# Jebao.net
KiCad netlist of a schematic drawn in EAGLE
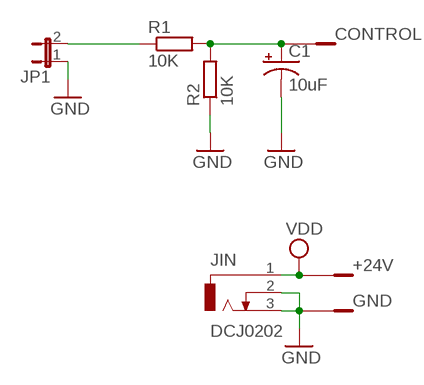
[diagram p0: schematic, sheet 1]

(export (version "E")
  (design (tool "Eeschema 10.0.6"))
  (components
    (comp (ref "+24V")
      (value "POWERPIN")
      (footprint "eagle-import:POWERPIN")
      (libsource (lib "eagle-import") (part "POWERPIN"))
    )
    (comp (ref "C1")
      (value "10uF")
      (footprint "eagle-import:A_3216-18R")
      (libsource (lib "eagle-import") (part "CPOL-USA/3216-18R"))
    )
    (comp (ref "CONTROL")
      (value "POWERPIN")
      (footprint "eagle-import:POWERPIN")
      (libsource (lib "eagle-import") (part "POWERPIN"))
    )
    (comp (ref "GND")
      (value "POWERPIN")
      (footprint "eagle-import:POWERPIN")
      (libsource (lib "eagle-import") (part "POWERPIN"))
    )
    (comp (ref "JIN")
      (value "DCJ0202")
      (footprint "eagle-import:DCJ0202")
      (libsource (lib "eagle-import") (part "DCJ0202"))
    )
    (comp (ref "JP1")
      (value "JP1E")
      (footprint "eagle-import:JP1")
      (libsource (lib "eagle-import") (part "JP1E"))
    )
    (comp (ref "R1")
      (value "10K")
      (footprint "eagle-import:R0805")
      (libsource (lib "eagle-import") (part "R-EU_R0805"))
    )
    (comp (ref "R2")
      (value "10K")
      (footprint "eagle-import:R0805")
      (libsource (lib "eagle-import") (part "R-EU_R0805"))
    )
  )
  (nets
    (net (code "1") (name "GND") (class "Default")
      (node (ref "C1") (pin "-") (pinfunction "-_-") (pintype "passive"))
      (node (ref "GND") (pin "1") (pinfunction "1_1") (pintype "bidirectional"))
      (node (ref "JIN") (pin "2") (pinfunction "2_2") (pintype "passive"))
      (node (ref "JIN") (pin "3") (pinfunction "3_3") (pintype "passive"))
      (node (ref "JP1") (pin "1") (pinfunction "1_1") (pintype "passive"))
      (node (ref "R2") (pin "1") (pinfunction "1_1") (pintype "passive"))
    )
    (net (code "2") (name "Net-(C1-Pad+)") (class "Default")
      (node (ref "C1") (pin "+") (pinfunction "+_+") (pintype "passive"))
      (node (ref "CONTROL") (pin "1") (pinfunction "1_1") (pintype "bidirectional"))
      (node (ref "R1") (pin "2") (pinfunction "2_2") (pintype "passive"))
      (node (ref "R2") (pin "2") (pinfunction "2_2") (pintype "passive"))
    )
    (net (code "3") (name "Net-(JP1-Pad2)") (class "Default")
      (node (ref "JP1") (pin "2") (pinfunction "2_2") (pintype "passive"))
      (node (ref "R1") (pin "1") (pinfunction "1_1") (pintype "passive"))
    )
    (net (code "4") (name "VDD") (class "Default")
      (node (ref "+24V") (pin "1") (pinfunction "1_1") (pintype "bidirectional"))
      (node (ref "JIN") (pin "1") (pinfunction "1_1") (pintype "passive"))
    )
  )
)
